# jam_Digital.net
KiCad netlist of a schematic drawn in EAGLE
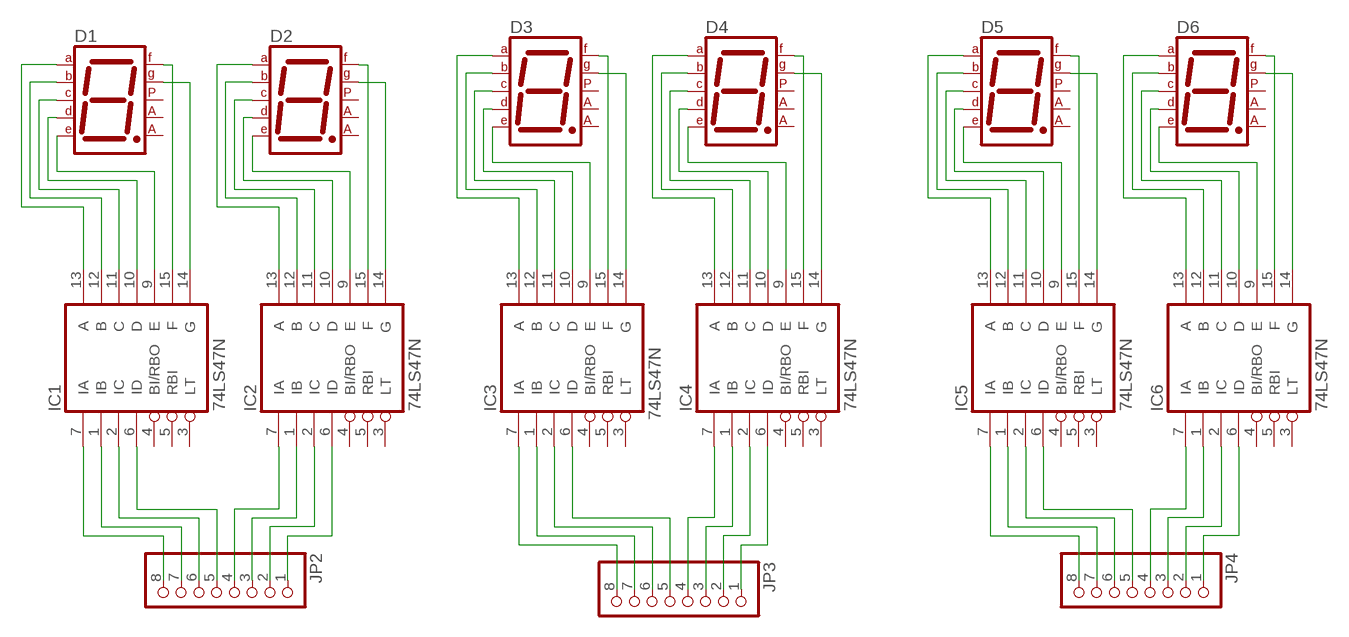
[diagram p0: schematic, sheet 1]

(export (version "E")
  (design (tool "Eeschema 10.0.6"))
  (components
    (comp (ref "D1")
      (value "7SEG-CA")
      (footprint "eagle-import:7SEG-13")
      (libsource (lib "eagle-import") (part "7SEG-CA"))
    )
    (comp (ref "D2")
      (value "7SEG-CA")
      (footprint "eagle-import:7SEG-13")
      (libsource (lib "eagle-import") (part "7SEG-CA"))
    )
    (comp (ref "D3")
      (value "7SEG-CA")
      (footprint "eagle-import:7SEG-13")
      (libsource (lib "eagle-import") (part "7SEG-CA"))
    )
    (comp (ref "D4")
      (value "7SEG-CA")
      (footprint "eagle-import:7SEG-13")
      (libsource (lib "eagle-import") (part "7SEG-CA"))
    )
    (comp (ref "D5")
      (value "7SEG-CA")
      (footprint "eagle-import:7SEG-13")
      (libsource (lib "eagle-import") (part "7SEG-CA"))
    )
    (comp (ref "D6")
      (value "7SEG-CA")
      (footprint "eagle-import:7SEG-13")
      (libsource (lib "eagle-import") (part "7SEG-CA"))
    )
    (comp (ref "IC1")
      (value "74LS47N")
      (footprint "eagle-import:DIL16")
      (libsource (lib "eagle-import") (part "7447NLS"))
    )
    (comp (ref "IC2")
      (value "74LS47N")
      (footprint "eagle-import:DIL16")
      (libsource (lib "eagle-import") (part "7447NLS"))
    )
    (comp (ref "IC3")
      (value "74LS47N")
      (footprint "eagle-import:DIL16")
      (libsource (lib "eagle-import") (part "7447NLS"))
    )
    (comp (ref "IC4")
      (value "74LS47N")
      (footprint "eagle-import:DIL16")
      (libsource (lib "eagle-import") (part "7447NLS"))
    )
    (comp (ref "IC5")
      (value "74LS47N")
      (footprint "eagle-import:DIL16")
      (libsource (lib "eagle-import") (part "7447NLS"))
    )
    (comp (ref "IC6")
      (value "74LS47N")
      (footprint "eagle-import:DIL16")
      (libsource (lib "eagle-import") (part "7447NLS"))
    )
    (comp (ref "JP2")
      (value "PINHD-1X8")
      (footprint "eagle-import:1X08")
      (libsource (lib "eagle-import") (part "PINHD-1X8"))
    )
    (comp (ref "JP3")
      (value "PINHD-1X8")
      (footprint "eagle-import:1X08")
      (libsource (lib "eagle-import") (part "PINHD-1X8"))
    )
    (comp (ref "JP4")
      (value "PINHD-1X8")
      (footprint "eagle-import:1X08")
      (libsource (lib "eagle-import") (part "PINHD-1X8"))
    )
  )
  (nets
    (net (code "1") (name "Net-(D1-A)") (class "Default")
      (node (ref "D1") (pin "7") (pinfunction "A_7") (pintype "passive"))
      (node (ref "IC1") (pin "13") (pinfunction "A_13") (pintype "output"))
    )
    (net (code "2") (name "Net-(D1-B)") (class "Default")
      (node (ref "D1") (pin "6") (pinfunction "B_6") (pintype "passive"))
      (node (ref "IC1") (pin "12") (pinfunction "B_12") (pintype "output"))
    )
    (net (code "3") (name "Net-(D1-C)") (class "Default")
      (node (ref "D1") (pin "4") (pinfunction "C_4") (pintype "passive"))
      (node (ref "IC1") (pin "11") (pinfunction "C_11") (pintype "output"))
    )
    (net (code "4") (name "Net-(D1-D)") (class "Default")
      (node (ref "D1") (pin "2") (pinfunction "D_2") (pintype "passive"))
      (node (ref "IC1") (pin "10") (pinfunction "D_10") (pintype "output"))
    )
    (net (code "5") (name "Net-(D1-E)") (class "Default")
      (node (ref "D1") (pin "1") (pinfunction "E_1") (pintype "passive"))
      (node (ref "IC1") (pin "9") (pinfunction "E_9") (pintype "output"))
    )
    (net (code "6") (name "Net-(D1-F)") (class "Default")
      (node (ref "D1") (pin "9") (pinfunction "F_9") (pintype "passive"))
      (node (ref "IC1") (pin "15") (pinfunction "F_15") (pintype "output"))
    )
    (net (code "7") (name "Net-(D1-G)") (class "Default")
      (node (ref "D1") (pin "10") (pinfunction "G_10") (pintype "passive"))
      (node (ref "IC1") (pin "14") (pinfunction "G_14") (pintype "output"))
    )
    (net (code "8") (name "Net-(D2-A)") (class "Default")
      (node (ref "D2") (pin "7") (pinfunction "A_7") (pintype "passive"))
      (node (ref "IC2") (pin "13") (pinfunction "A_13") (pintype "output"))
    )
    (net (code "9") (name "Net-(D2-B)") (class "Default")
      (node (ref "D2") (pin "6") (pinfunction "B_6") (pintype "passive"))
      (node (ref "IC2") (pin "12") (pinfunction "B_12") (pintype "output"))
    )
    (net (code "10") (name "Net-(D2-C)") (class "Default")
      (node (ref "D2") (pin "4") (pinfunction "C_4") (pintype "passive"))
      (node (ref "IC2") (pin "11") (pinfunction "C_11") (pintype "output"))
    )
    (net (code "11") (name "Net-(D2-D)") (class "Default")
      (node (ref "D2") (pin "2") (pinfunction "D_2") (pintype "passive"))
      (node (ref "IC2") (pin "10") (pinfunction "D_10") (pintype "output"))
    )
    (net (code "12") (name "Net-(D2-E)") (class "Default")
      (node (ref "D2") (pin "1") (pinfunction "E_1") (pintype "passive"))
      (node (ref "IC2") (pin "9") (pinfunction "E_9") (pintype "output"))
    )
    (net (code "13") (name "Net-(D2-F)") (class "Default")
      (node (ref "D2") (pin "9") (pinfunction "F_9") (pintype "passive"))
      (node (ref "IC2") (pin "15") (pinfunction "F_15") (pintype "output"))
    )
    (net (code "14") (name "Net-(D2-G)") (class "Default")
      (node (ref "D2") (pin "10") (pinfunction "G_10") (pintype "passive"))
      (node (ref "IC2") (pin "14") (pinfunction "G_14") (pintype "output"))
    )
    (net (code "15") (name "Net-(D3-A)") (class "Default")
      (node (ref "D3") (pin "7") (pinfunction "A_7") (pintype "passive"))
      (node (ref "IC3") (pin "13") (pinfunction "A_13") (pintype "output"))
    )
    (net (code "16") (name "Net-(D3-B)") (class "Default")
      (node (ref "D3") (pin "6") (pinfunction "B_6") (pintype "passive"))
      (node (ref "IC3") (pin "12") (pinfunction "B_12") (pintype "output"))
    )
    (net (code "17") (name "Net-(D3-C)") (class "Default")
      (node (ref "D3") (pin "4") (pinfunction "C_4") (pintype "passive"))
      (node (ref "IC3") (pin "11") (pinfunction "C_11") (pintype "output"))
    )
    (net (code "18") (name "Net-(D3-D)") (class "Default")
      (node (ref "D3") (pin "2") (pinfunction "D_2") (pintype "passive"))
      (node (ref "IC3") (pin "10") (pinfunction "D_10") (pintype "output"))
    )
    (net (code "19") (name "Net-(D3-E)") (class "Default")
      (node (ref "D3") (pin "1") (pinfunction "E_1") (pintype "passive"))
      (node (ref "IC3") (pin "9") (pinfunction "E_9") (pintype "output"))
    )
    (net (code "20") (name "Net-(D3-F)") (class "Default")
      (node (ref "D3") (pin "9") (pinfunction "F_9") (pintype "passive"))
      (node (ref "IC3") (pin "15") (pinfunction "F_15") (pintype "output"))
    )
    (net (code "21") (name "Net-(D3-G)") (class "Default")
      (node (ref "D3") (pin "10") (pinfunction "G_10") (pintype "passive"))
      (node (ref "IC3") (pin "14") (pinfunction "G_14") (pintype "output"))
    )
    (net (code "22") (name "Net-(D4-A)") (class "Default")
      (node (ref "D4") (pin "7") (pinfunction "A_7") (pintype "passive"))
      (node (ref "IC4") (pin "13") (pinfunction "A_13") (pintype "output"))
    )
    (net (code "23") (name "Net-(D4-B)") (class "Default")
      (node (ref "D4") (pin "6") (pinfunction "B_6") (pintype "passive"))
      (node (ref "IC4") (pin "12") (pinfunction "B_12") (pintype "output"))
    )
    (net (code "24") (name "Net-(D4-C)") (class "Default")
      (node (ref "D4") (pin "4") (pinfunction "C_4") (pintype "passive"))
      (node (ref "IC4") (pin "11") (pinfunction "C_11") (pintype "output"))
    )
    (net (code "25") (name "Net-(D4-D)") (class "Default")
      (node (ref "D4") (pin "2") (pinfunction "D_2") (pintype "passive"))
      (node (ref "IC4") (pin "10") (pinfunction "D_10") (pintype "output"))
    )
    (net (code "26") (name "Net-(D4-E)") (class "Default")
      (node (ref "D4") (pin "1") (pinfunction "E_1") (pintype "passive"))
      (node (ref "IC4") (pin "9") (pinfunction "E_9") (pintype "output"))
    )
    (net (code "27") (name "Net-(D4-F)") (class "Default")
      (node (ref "D4") (pin "9") (pinfunction "F_9") (pintype "passive"))
      (node (ref "IC4") (pin "15") (pinfunction "F_15") (pintype "output"))
    )
    (net (code "28") (name "Net-(D4-G)") (class "Default")
      (node (ref "D4") (pin "10") (pinfunction "G_10") (pintype "passive"))
      (node (ref "IC4") (pin "14") (pinfunction "G_14") (pintype "output"))
    )
    (net (code "29") (name "Net-(D5-A)") (class "Default")
      (node (ref "D5") (pin "7") (pinfunction "A_7") (pintype "passive"))
      (node (ref "IC5") (pin "13") (pinfunction "A_13") (pintype "output"))
    )
    (net (code "30") (name "Net-(D5-B)") (class "Default")
      (node (ref "D5") (pin "6") (pinfunction "B_6") (pintype "passive"))
      (node (ref "IC5") (pin "12") (pinfunction "B_12") (pintype "output"))
    )
    (net (code "31") (name "Net-(D5-C)") (class "Default")
      (node (ref "D5") (pin "4") (pinfunction "C_4") (pintype "passive"))
      (node (ref "IC5") (pin "11") (pinfunction "C_11") (pintype "output"))
    )
    (net (code "32") (name "Net-(D5-D)") (class "Default")
      (node (ref "D5") (pin "2") (pinfunction "D_2") (pintype "passive"))
      (node (ref "IC5") (pin "10") (pinfunction "D_10") (pintype "output"))
    )
    (net (code "33") (name "Net-(D5-E)") (class "Default")
      (node (ref "D5") (pin "1") (pinfunction "E_1") (pintype "passive"))
      (node (ref "IC5") (pin "9") (pinfunction "E_9") (pintype "output"))
    )
    (net (code "34") (name "Net-(D5-F)") (class "Default")
      (node (ref "D5") (pin "9") (pinfunction "F_9") (pintype "passive"))
      (node (ref "IC5") (pin "15") (pinfunction "F_15") (pintype "output"))
    )
    (net (code "35") (name "Net-(D5-G)") (class "Default")
      (node (ref "D5") (pin "10") (pinfunction "G_10") (pintype "passive"))
      (node (ref "IC5") (pin "14") (pinfunction "G_14") (pintype "output"))
    )
    (net (code "36") (name "Net-(D6-A)") (class "Default")
      (node (ref "D6") (pin "7") (pinfunction "A_7") (pintype "passive"))
      (node (ref "IC6") (pin "13") (pinfunction "A_13") (pintype "output"))
    )
    (net (code "37") (name "Net-(D6-B)") (class "Default")
      (node (ref "D6") (pin "6") (pinfunction "B_6") (pintype "passive"))
      (node (ref "IC6") (pin "12") (pinfunction "B_12") (pintype "output"))
    )
    (net (code "38") (name "Net-(D6-C)") (class "Default")
      (node (ref "D6") (pin "4") (pinfunction "C_4") (pintype "passive"))
      (node (ref "IC6") (pin "11") (pinfunction "C_11") (pintype "output"))
    )
    (net (code "39") (name "Net-(D6-D)") (class "Default")
      (node (ref "D6") (pin "2") (pinfunction "D_2") (pintype "passive"))
      (node (ref "IC6") (pin "10") (pinfunction "D_10") (pintype "output"))
    )
    (net (code "40") (name "Net-(D6-E)") (class "Default")
      (node (ref "D6") (pin "1") (pinfunction "E_1") (pintype "passive"))
      (node (ref "IC6") (pin "9") (pinfunction "E_9") (pintype "output"))
    )
    (net (code "41") (name "Net-(D6-F)") (class "Default")
      (node (ref "D6") (pin "9") (pinfunction "F_9") (pintype "passive"))
      (node (ref "IC6") (pin "15") (pinfunction "F_15") (pintype "output"))
    )
    (net (code "42") (name "Net-(D6-G)") (class "Default")
      (node (ref "D6") (pin "10") (pinfunction "G_10") (pintype "passive"))
      (node (ref "IC6") (pin "14") (pinfunction "G_14") (pintype "output"))
    )
    (net (code "43") (name "Net-(IC1A-IA)") (class "Default")
      (node (ref "IC1") (pin "7") (pinfunction "IA_7") (pintype "input"))
      (node (ref "JP2") (pin "8") (pinfunction "8_8") (pintype "passive"))
    )
    (net (code "44") (name "Net-(IC1A-IB)") (class "Default")
      (node (ref "IC1") (pin "1") (pinfunction "IB_1") (pintype "input"))
      (node (ref "JP2") (pin "7") (pinfunction "7_7") (pintype "passive"))
    )
    (net (code "45") (name "Net-(IC1A-IC)") (class "Default")
      (node (ref "IC1") (pin "2") (pinfunction "IC_2") (pintype "input"))
      (node (ref "JP2") (pin "6") (pinfunction "6_6") (pintype "passive"))
    )
    (net (code "46") (name "Net-(IC1A-ID)") (class "Default")
      (node (ref "IC1") (pin "6") (pinfunction "ID_6") (pintype "input"))
      (node (ref "JP2") (pin "5") (pinfunction "5_5") (pintype "passive"))
    )
    (net (code "47") (name "Net-(IC2A-IA)") (class "Default")
      (node (ref "IC2") (pin "7") (pinfunction "IA_7") (pintype "input"))
      (node (ref "JP2") (pin "4") (pinfunction "4_4") (pintype "passive"))
    )
    (net (code "48") (name "Net-(IC2A-IB)") (class "Default")
      (node (ref "IC2") (pin "1") (pinfunction "IB_1") (pintype "input"))
      (node (ref "JP2") (pin "3") (pinfunction "3_3") (pintype "passive"))
    )
    (net (code "49") (name "Net-(IC2A-IC)") (class "Default")
      (node (ref "IC2") (pin "2") (pinfunction "IC_2") (pintype "input"))
      (node (ref "JP2") (pin "2") (pinfunction "2_2") (pintype "passive"))
    )
    (net (code "50") (name "Net-(IC2A-ID)") (class "Default")
      (node (ref "IC2") (pin "6") (pinfunction "ID_6") (pintype "input"))
      (node (ref "JP2") (pin "1") (pinfunction "1_1") (pintype "passive"))
    )
    (net (code "51") (name "Net-(IC3A-IA)") (class "Default")
      (node (ref "IC3") (pin "7") (pinfunction "IA_7") (pintype "input"))
      (node (ref "JP3") (pin "8") (pinfunction "8_8") (pintype "passive"))
    )
    (net (code "52") (name "Net-(IC3A-IB)") (class "Default")
      (node (ref "IC3") (pin "1") (pinfunction "IB_1") (pintype "input"))
      (node (ref "JP3") (pin "7") (pinfunction "7_7") (pintype "passive"))
    )
    (net (code "53") (name "Net-(IC3A-IC)") (class "Default")
      (node (ref "IC3") (pin "2") (pinfunction "IC_2") (pintype "input"))
      (node (ref "JP3") (pin "6") (pinfunction "6_6") (pintype "passive"))
    )
    (net (code "54") (name "Net-(IC3A-ID)") (class "Default")
      (node (ref "IC3") (pin "6") (pinfunction "ID_6") (pintype "input"))
      (node (ref "JP3") (pin "5") (pinfunction "5_5") (pintype "passive"))
    )
    (net (code "55") (name "Net-(IC4A-IA)") (class "Default")
      (node (ref "IC4") (pin "7") (pinfunction "IA_7") (pintype "input"))
      (node (ref "JP3") (pin "4") (pinfunction "4_4") (pintype "passive"))
    )
    (net (code "56") (name "Net-(IC4A-IB)") (class "Default")
      (node (ref "IC4") (pin "1") (pinfunction "IB_1") (pintype "input"))
      (node (ref "JP3") (pin "3") (pinfunction "3_3") (pintype "passive"))
    )
    (net (code "57") (name "Net-(IC4A-IC)") (class "Default")
      (node (ref "IC4") (pin "2") (pinfunction "IC_2") (pintype "input"))
      (node (ref "JP3") (pin "2") (pinfunction "2_2") (pintype "passive"))
    )
    (net (code "58") (name "Net-(IC4A-ID)") (class "Default")
      (node (ref "IC4") (pin "6") (pinfunction "ID_6") (pintype "input"))
      (node (ref "JP3") (pin "1") (pinfunction "1_1") (pintype "passive"))
    )
    (net (code "59") (name "Net-(IC5A-IA)") (class "Default")
      (node (ref "IC5") (pin "7") (pinfunction "IA_7") (pintype "input"))
      (node (ref "JP4") (pin "8") (pinfunction "8_8") (pintype "passive"))
    )
    (net (code "60") (name "Net-(IC5A-IB)") (class "Default")
      (node (ref "IC5") (pin "1") (pinfunction "IB_1") (pintype "input"))
      (node (ref "JP4") (pin "7") (pinfunction "7_7") (pintype "passive"))
    )
    (net (code "61") (name "Net-(IC5A-IC)") (class "Default")
      (node (ref "IC5") (pin "2") (pinfunction "IC_2") (pintype "input"))
      (node (ref "JP4") (pin "6") (pinfunction "6_6") (pintype "passive"))
    )
    (net (code "62") (name "Net-(IC5A-ID)") (class "Default")
      (node (ref "IC5") (pin "6") (pinfunction "ID_6") (pintype "input"))
      (node (ref "JP4") (pin "5") (pinfunction "5_5") (pintype "passive"))
    )
    (net (code "63") (name "Net-(IC6A-IA)") (class "Default")
      (node (ref "IC6") (pin "7") (pinfunction "IA_7") (pintype "input"))
      (node (ref "JP4") (pin "4") (pinfunction "4_4") (pintype "passive"))
    )
    (net (code "64") (name "Net-(IC6A-IB)") (class "Default")
      (node (ref "IC6") (pin "1") (pinfunction "IB_1") (pintype "input"))
      (node (ref "JP4") (pin "3") (pinfunction "3_3") (pintype "passive"))
    )
    (net (code "65") (name "Net-(IC6A-IC)") (class "Default")
      (node (ref "IC6") (pin "2") (pinfunction "IC_2") (pintype "input"))
      (node (ref "JP4") (pin "2") (pinfunction "2_2") (pintype "passive"))
    )
    (net (code "66") (name "Net-(IC6A-ID)") (class "Default")
      (node (ref "IC6") (pin "6") (pinfunction "ID_6") (pintype "input"))
      (node (ref "JP4") (pin "1") (pinfunction "1_1") (pintype "passive"))
    )
    (net (code "67") (name "unconnected-(D1-CA1-Pad3)") (class "Default")
      (node (ref "D1") (pin "3") (pinfunction "CA1_3") (pintype "passive"))
    )
    (net (code "68") (name "unconnected-(D1-CA2-Pad8)") (class "Default")
      (node (ref "D1") (pin "8") (pinfunction "CA2_8") (pintype "passive"))
    )
    (net (code "69") (name "unconnected-(D1-DP-Pad5)") (class "Default")
      (node (ref "D1") (pin "5") (pinfunction "DP_5") (pintype "passive"))
    )
    (net (code "70") (name "unconnected-(D2-CA1-Pad3)") (class "Default")
      (node (ref "D2") (pin "3") (pinfunction "CA1_3") (pintype "passive"))
    )
    (net (code "71") (name "unconnected-(D2-CA2-Pad8)") (class "Default")
      (node (ref "D2") (pin "8") (pinfunction "CA2_8") (pintype "passive"))
    )
    (net (code "72") (name "unconnected-(D2-DP-Pad5)") (class "Default")
      (node (ref "D2") (pin "5") (pinfunction "DP_5") (pintype "passive"))
    )
    (net (code "73") (name "unconnected-(D3-CA1-Pad3)") (class "Default")
      (node (ref "D3") (pin "3") (pinfunction "CA1_3") (pintype "passive"))
    )
    (net (code "74") (name "unconnected-(D3-CA2-Pad8)") (class "Default")
      (node (ref "D3") (pin "8") (pinfunction "CA2_8") (pintype "passive"))
    )
    (net (code "75") (name "unconnected-(D3-DP-Pad5)") (class "Default")
      (node (ref "D3") (pin "5") (pinfunction "DP_5") (pintype "passive"))
    )
    (net (code "76") (name "unconnected-(D4-CA1-Pad3)") (class "Default")
      (node (ref "D4") (pin "3") (pinfunction "CA1_3") (pintype "passive"))
    )
    (net (code "77") (name "unconnected-(D4-CA2-Pad8)") (class "Default")
      (node (ref "D4") (pin "8") (pinfunction "CA2_8") (pintype "passive"))
    )
    (net (code "78") (name "unconnected-(D4-DP-Pad5)") (class "Default")
      (node (ref "D4") (pin "5") (pinfunction "DP_5") (pintype "passive"))
    )
    (net (code "79") (name "unconnected-(D5-CA1-Pad3)") (class "Default")
      (node (ref "D5") (pin "3") (pinfunction "CA1_3") (pintype "passive"))
    )
    (net (code "80") (name "unconnected-(D5-CA2-Pad8)") (class "Default")
      (node (ref "D5") (pin "8") (pinfunction "CA2_8") (pintype "passive"))
    )
    (net (code "81") (name "unconnected-(D5-DP-Pad5)") (class "Default")
      (node (ref "D5") (pin "5") (pinfunction "DP_5") (pintype "passive"))
    )
    (net (code "82") (name "unconnected-(D6-CA1-Pad3)") (class "Default")
      (node (ref "D6") (pin "3") (pinfunction "CA1_3") (pintype "passive"))
    )
    (net (code "83") (name "unconnected-(D6-CA2-Pad8)") (class "Default")
      (node (ref "D6") (pin "8") (pinfunction "CA2_8") (pintype "passive"))
    )
    (net (code "84") (name "unconnected-(D6-DP-Pad5)") (class "Default")
      (node (ref "D6") (pin "5") (pinfunction "DP_5") (pintype "passive"))
    )
    (net (code "85") (name "unconnected-(IC1A-BI{slash}RBO-Pad4)") (class "Default")
      (node (ref "IC1") (pin "4") (pinfunction "BI/RBO_4") (pintype "input"))
    )
    (net (code "86") (name "unconnected-(IC1A-LT-Pad3)") (class "Default")
      (node (ref "IC1") (pin "3") (pinfunction "LT_3") (pintype "input"))
    )
    (net (code "87") (name "unconnected-(IC1A-RBI-Pad5)") (class "Default")
      (node (ref "IC1") (pin "5") (pinfunction "RBI_5") (pintype "input"))
    )
    (net (code "88") (name "unconnected-(IC2A-BI{slash}RBO-Pad4)") (class "Default")
      (node (ref "IC2") (pin "4") (pinfunction "BI/RBO_4") (pintype "input"))
    )
    (net (code "89") (name "unconnected-(IC2A-LT-Pad3)") (class "Default")
      (node (ref "IC2") (pin "3") (pinfunction "LT_3") (pintype "input"))
    )
    (net (code "90") (name "unconnected-(IC2A-RBI-Pad5)") (class "Default")
      (node (ref "IC2") (pin "5") (pinfunction "RBI_5") (pintype "input"))
    )
    (net (code "91") (name "unconnected-(IC3A-BI{slash}RBO-Pad4)") (class "Default")
      (node (ref "IC3") (pin "4") (pinfunction "BI/RBO_4") (pintype "input"))
    )
    (net (code "92") (name "unconnected-(IC3A-LT-Pad3)") (class "Default")
      (node (ref "IC3") (pin "3") (pinfunction "LT_3") (pintype "input"))
    )
    (net (code "93") (name "unconnected-(IC3A-RBI-Pad5)") (class "Default")
      (node (ref "IC3") (pin "5") (pinfunction "RBI_5") (pintype "input"))
    )
    (net (code "94") (name "unconnected-(IC4A-BI{slash}RBO-Pad4)") (class "Default")
      (node (ref "IC4") (pin "4") (pinfunction "BI/RBO_4") (pintype "input"))
    )
    (net (code "95") (name "unconnected-(IC4A-LT-Pad3)") (class "Default")
      (node (ref "IC4") (pin "3") (pinfunction "LT_3") (pintype "input"))
    )
    (net (code "96") (name "unconnected-(IC4A-RBI-Pad5)") (class "Default")
      (node (ref "IC4") (pin "5") (pinfunction "RBI_5") (pintype "input"))
    )
    (net (code "97") (name "unconnected-(IC5A-BI{slash}RBO-Pad4)") (class "Default")
      (node (ref "IC5") (pin "4") (pinfunction "BI/RBO_4") (pintype "input"))
    )
    (net (code "98") (name "unconnected-(IC5A-LT-Pad3)") (class "Default")
      (node (ref "IC5") (pin "3") (pinfunction "LT_3") (pintype "input"))
    )
    (net (code "99") (name "unconnected-(IC5A-RBI-Pad5)") (class "Default")
      (node (ref "IC5") (pin "5") (pinfunction "RBI_5") (pintype "input"))
    )
    (net (code "100") (name "unconnected-(IC6A-BI{slash}RBO-Pad4)") (class "Default")
      (node (ref "IC6") (pin "4") (pinfunction "BI/RBO_4") (pintype "input"))
    )
    (net (code "101") (name "unconnected-(IC6A-LT-Pad3)") (class "Default")
      (node (ref "IC6") (pin "3") (pinfunction "LT_3") (pintype "input"))
    )
    (net (code "102") (name "unconnected-(IC6A-RBI-Pad5)") (class "Default")
      (node (ref "IC6") (pin "5") (pinfunction "RBI_5") (pintype "input"))
    )
  )
)
